# MaximAnalogSignalConnections.net
KiCad netlist of a schematic drawn in Altium Designer
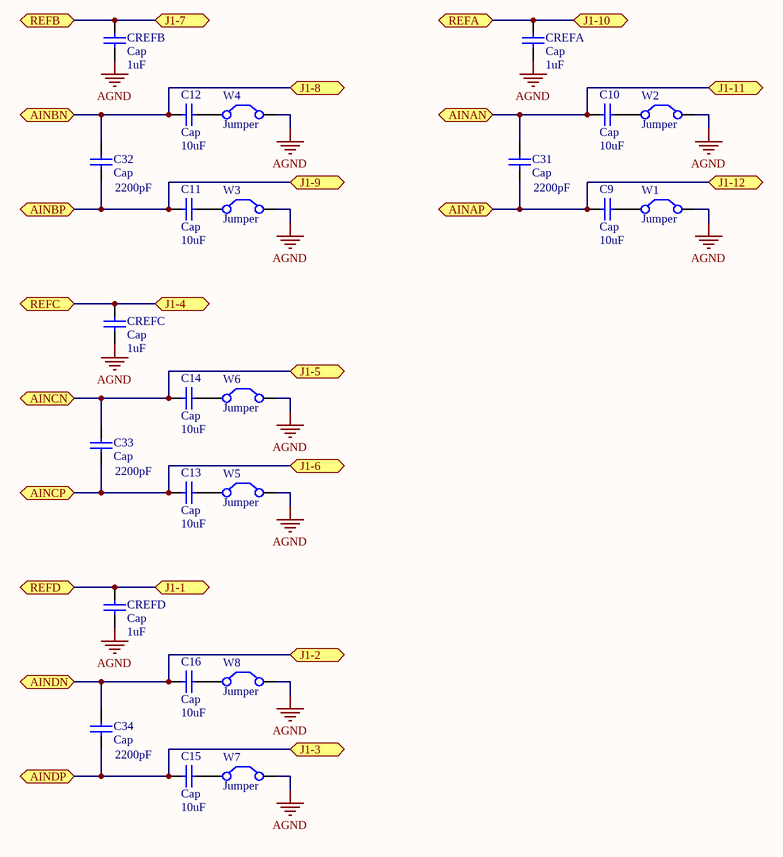
[diagram p0: MaximAnalogSignalConnections.SchDoc]

(export (version "E")
  (design (tool "Eeschema 10.0.6"))
  (components
    (comp (ref "C9")
      (value "Cap")
      (footprint "RAD-0.3")
      (description "Capacitor")
      (fields (field (name "ALTIUM_VALUE") "10uF") (field (name "PUBLISHER") "Altium Limited"))
      (libsource (lib "Miscellaneous Devices") (part "Cap"))
    )
    (comp (ref "C10")
      (value "Cap")
      (footprint "RAD-0.3")
      (description "Capacitor")
      (fields (field (name "ALTIUM_VALUE") "10uF") (field (name "PUBLISHER") "Altium Limited"))
      (libsource (lib "Miscellaneous Devices") (part "Cap"))
    )
    (comp (ref "C11")
      (value "Cap")
      (footprint "RAD-0.3")
      (description "Capacitor")
      (fields (field (name "ALTIUM_VALUE") "10uF") (field (name "PUBLISHER") "Altium Limited"))
      (libsource (lib "Miscellaneous Devices") (part "Cap"))
    )
    (comp (ref "C12")
      (value "Cap")
      (footprint "RAD-0.3")
      (description "Capacitor")
      (fields (field (name "ALTIUM_VALUE") "10uF") (field (name "PUBLISHER") "Altium Limited"))
      (libsource (lib "Miscellaneous Devices") (part "Cap"))
    )
    (comp (ref "C13")
      (value "Cap")
      (footprint "RAD-0.3")
      (description "Capacitor")
      (fields (field (name "ALTIUM_VALUE") "10uF") (field (name "PUBLISHER") "Altium Limited"))
      (libsource (lib "Miscellaneous Devices") (part "Cap"))
    )
    (comp (ref "C14")
      (value "Cap")
      (footprint "RAD-0.3")
      (description "Capacitor")
      (fields (field (name "ALTIUM_VALUE") "10uF") (field (name "PUBLISHER") "Altium Limited"))
      (libsource (lib "Miscellaneous Devices") (part "Cap"))
    )
    (comp (ref "C15")
      (value "Cap")
      (footprint "RAD-0.3")
      (description "Capacitor")
      (fields (field (name "ALTIUM_VALUE") "10uF") (field (name "PUBLISHER") "Altium Limited"))
      (libsource (lib "Miscellaneous Devices") (part "Cap"))
    )
    (comp (ref "C16")
      (value "Cap")
      (footprint "RAD-0.3")
      (description "Capacitor")
      (fields (field (name "ALTIUM_VALUE") "10uF") (field (name "PUBLISHER") "Altium Limited"))
      (libsource (lib "Miscellaneous Devices") (part "Cap"))
    )
    (comp (ref "C31")
      (value "Cap")
      (footprint "RAD-0.3")
      (description "Capacitor")
      (fields (field (name "ALTIUM_VALUE") "2200pF") (field (name "PUBLISHER") "Altium Limited"))
      (libsource (lib "Miscellaneous Devices") (part "Cap"))
    )
    (comp (ref "C32")
      (value "Cap")
      (footprint "RAD-0.3")
      (description "Capacitor")
      (fields (field (name "ALTIUM_VALUE") "2200pF") (field (name "PUBLISHER") "Altium Limited"))
      (libsource (lib "Miscellaneous Devices") (part "Cap"))
    )
    (comp (ref "C33")
      (value "Cap")
      (footprint "RAD-0.3")
      (description "Capacitor")
      (fields (field (name "ALTIUM_VALUE") "2200pF") (field (name "PUBLISHER") "Altium Limited"))
      (libsource (lib "Miscellaneous Devices") (part "Cap"))
    )
    (comp (ref "C34")
      (value "Cap")
      (footprint "RAD-0.3")
      (description "Capacitor")
      (fields (field (name "ALTIUM_VALUE") "2200pF") (field (name "PUBLISHER") "Altium Limited"))
      (libsource (lib "Miscellaneous Devices") (part "Cap"))
    )
    (comp (ref "CREFA")
      (value "Cap")
      (footprint "RAD-0.3")
      (description "Capacitor")
      (fields (field (name "ALTIUM_VALUE") "1uF") (field (name "PUBLISHER") "Altium Limited"))
      (libsource (lib "Miscellaneous Devices") (part "Cap"))
    )
    (comp (ref "CREFB")
      (value "Cap")
      (footprint "RAD-0.3")
      (description "Capacitor")
      (fields (field (name "ALTIUM_VALUE") "1uF") (field (name "PUBLISHER") "Altium Limited"))
      (libsource (lib "Miscellaneous Devices") (part "Cap"))
    )
    (comp (ref "CREFC")
      (value "Cap")
      (footprint "RAD-0.3")
      (description "Capacitor")
      (fields (field (name "ALTIUM_VALUE") "1uF") (field (name "PUBLISHER") "Altium Limited"))
      (libsource (lib "Miscellaneous Devices") (part "Cap"))
    )
    (comp (ref "CREFD")
      (value "Cap")
      (footprint "RAD-0.3")
      (description "Capacitor")
      (fields (field (name "ALTIUM_VALUE") "1uF") (field (name "PUBLISHER") "Altium Limited"))
      (libsource (lib "Miscellaneous Devices") (part "Cap"))
    )
    (comp (ref "W1")
      (value "Jumper")
      (footprint "RAD-0.2")
      (description "Jumper Wire")
      (fields (field (name "PUBLISHER") "Altium Limited"))
      (libsource (lib "Miscellaneous Devices") (part "Jumper"))
    )
    (comp (ref "W2")
      (value "Jumper")
      (footprint "RAD-0.2")
      (description "Jumper Wire")
      (fields (field (name "PUBLISHER") "Altium Limited"))
      (libsource (lib "Miscellaneous Devices") (part "Jumper"))
    )
    (comp (ref "W3")
      (value "Jumper")
      (footprint "RAD-0.2")
      (description "Jumper Wire")
      (fields (field (name "PUBLISHER") "Altium Limited"))
      (libsource (lib "Miscellaneous Devices") (part "Jumper"))
    )
    (comp (ref "W4")
      (value "Jumper")
      (footprint "RAD-0.2")
      (description "Jumper Wire")
      (fields (field (name "PUBLISHER") "Altium Limited"))
      (libsource (lib "Miscellaneous Devices") (part "Jumper"))
    )
    (comp (ref "W5")
      (value "Jumper")
      (footprint "RAD-0.2")
      (description "Jumper Wire")
      (fields (field (name "PUBLISHER") "Altium Limited"))
      (libsource (lib "Miscellaneous Devices") (part "Jumper"))
    )
    (comp (ref "W6")
      (value "Jumper")
      (footprint "RAD-0.2")
      (description "Jumper Wire")
      (fields (field (name "PUBLISHER") "Altium Limited"))
      (libsource (lib "Miscellaneous Devices") (part "Jumper"))
    )
    (comp (ref "W7")
      (value "Jumper")
      (footprint "RAD-0.2")
      (description "Jumper Wire")
      (fields (field (name "PUBLISHER") "Altium Limited"))
      (libsource (lib "Miscellaneous Devices") (part "Jumper"))
    )
    (comp (ref "W8")
      (value "Jumper")
      (footprint "RAD-0.2")
      (description "Jumper Wire")
      (fields (field (name "PUBLISHER") "Altium Limited"))
      (libsource (lib "Miscellaneous Devices") (part "Jumper"))
    )
  )
  (nets
    (net (code "1") (name "/AINAN") (class "Default")
      (node (ref "C10") (pin "2") (pinfunction "2_2") (pintype "passive"))
      (node (ref "C31") (pin "2") (pinfunction "2_2") (pintype "passive"))
    )
    (net (code "2") (name "/AINAP") (class "Default")
      (node (ref "C31") (pin "1") (pinfunction "1_1") (pintype "passive"))
      (node (ref "C9") (pin "2") (pinfunction "2_2") (pintype "passive"))
    )
    (net (code "3") (name "/AINBN") (class "Default")
      (node (ref "C12") (pin "2") (pinfunction "2_2") (pintype "passive"))
      (node (ref "C32") (pin "2") (pinfunction "2_2") (pintype "passive"))
    )
    (net (code "4") (name "/AINBP") (class "Default")
      (node (ref "C11") (pin "2") (pinfunction "2_2") (pintype "passive"))
      (node (ref "C32") (pin "1") (pinfunction "1_1") (pintype "passive"))
    )
    (net (code "5") (name "/AINCN") (class "Default")
      (node (ref "C14") (pin "2") (pinfunction "2_2") (pintype "passive"))
      (node (ref "C33") (pin "2") (pinfunction "2_2") (pintype "passive"))
    )
    (net (code "6") (name "/AINCP") (class "Default")
      (node (ref "C13") (pin "2") (pinfunction "2_2") (pintype "passive"))
      (node (ref "C33") (pin "1") (pinfunction "1_1") (pintype "passive"))
    )
    (net (code "7") (name "/AINDN") (class "Default")
      (node (ref "C16") (pin "2") (pinfunction "2_2") (pintype "passive"))
      (node (ref "C34") (pin "2") (pinfunction "2_2") (pintype "passive"))
    )
    (net (code "8") (name "/AINDP") (class "Default")
      (node (ref "C15") (pin "2") (pinfunction "2_2") (pintype "passive"))
      (node (ref "C34") (pin "1") (pinfunction "1_1") (pintype "passive"))
    )
    (net (code "9") (name "/J1-1") (class "Default")
      (node (ref "CREFD") (pin "2") (pinfunction "2_2") (pintype "passive"))
    )
    (net (code "10") (name "/J1-4") (class "Default")
      (node (ref "CREFC") (pin "2") (pinfunction "2_2") (pintype "passive"))
    )
    (net (code "11") (name "/J1-7") (class "Default")
      (node (ref "CREFB") (pin "2") (pinfunction "2_2") (pintype "passive"))
    )
    (net (code "12") (name "/J1-10") (class "Default")
      (node (ref "CREFA") (pin "2") (pinfunction "2_2") (pintype "passive"))
    )
    (net (code "13") (name "AGND") (class "Default")
      (node (ref "CREFA") (pin "1") (pinfunction "1_1") (pintype "passive"))
      (node (ref "CREFB") (pin "1") (pinfunction "1_1") (pintype "passive"))
      (node (ref "CREFC") (pin "1") (pinfunction "1_1") (pintype "passive"))
      (node (ref "CREFD") (pin "1") (pinfunction "1_1") (pintype "passive"))
      (node (ref "W1") (pin "2") (pinfunction "C2_2") (pintype "passive"))
      (node (ref "W2") (pin "2") (pinfunction "C2_2") (pintype "passive"))
      (node (ref "W3") (pin "2") (pinfunction "C2_2") (pintype "passive"))
      (node (ref "W4") (pin "2") (pinfunction "C2_2") (pintype "passive"))
      (node (ref "W5") (pin "2") (pinfunction "C2_2") (pintype "passive"))
      (node (ref "W6") (pin "2") (pinfunction "C2_2") (pintype "passive"))
      (node (ref "W7") (pin "2") (pinfunction "C2_2") (pintype "passive"))
      (node (ref "W8") (pin "2") (pinfunction "C2_2") (pintype "passive"))
    )
    (net (code "14") (name "Net-(W1-C1)") (class "Default")
      (node (ref "C9") (pin "1") (pinfunction "1_1") (pintype "passive"))
      (node (ref "W1") (pin "1") (pinfunction "C1_1") (pintype "passive"))
    )
    (net (code "15") (name "Net-(W2-C1)") (class "Default")
      (node (ref "C10") (pin "1") (pinfunction "1_1") (pintype "passive"))
      (node (ref "W2") (pin "1") (pinfunction "C1_1") (pintype "passive"))
    )
    (net (code "16") (name "Net-(W3-C1)") (class "Default")
      (node (ref "C11") (pin "1") (pinfunction "1_1") (pintype "passive"))
      (node (ref "W3") (pin "1") (pinfunction "C1_1") (pintype "passive"))
    )
    (net (code "17") (name "Net-(W4-C1)") (class "Default")
      (node (ref "C12") (pin "1") (pinfunction "1_1") (pintype "passive"))
      (node (ref "W4") (pin "1") (pinfunction "C1_1") (pintype "passive"))
    )
    (net (code "18") (name "Net-(W5-C1)") (class "Default")
      (node (ref "C13") (pin "1") (pinfunction "1_1") (pintype "passive"))
      (node (ref "W5") (pin "1") (pinfunction "C1_1") (pintype "passive"))
    )
    (net (code "19") (name "Net-(W6-C1)") (class "Default")
      (node (ref "C14") (pin "1") (pinfunction "1_1") (pintype "passive"))
      (node (ref "W6") (pin "1") (pinfunction "C1_1") (pintype "passive"))
    )
    (net (code "20") (name "Net-(W7-C1)") (class "Default")
      (node (ref "C15") (pin "1") (pinfunction "1_1") (pintype "passive"))
      (node (ref "W7") (pin "1") (pinfunction "C1_1") (pintype "passive"))
    )
    (net (code "21") (name "Net-(W8-C1)") (class "Default")
      (node (ref "C16") (pin "1") (pinfunction "1_1") (pintype "passive"))
      (node (ref "W8") (pin "1") (pinfunction "C1_1") (pintype "passive"))
    )
  )
)
